# ResetCircuit.net
KiCad netlist of a schematic drawn in Altium Designer
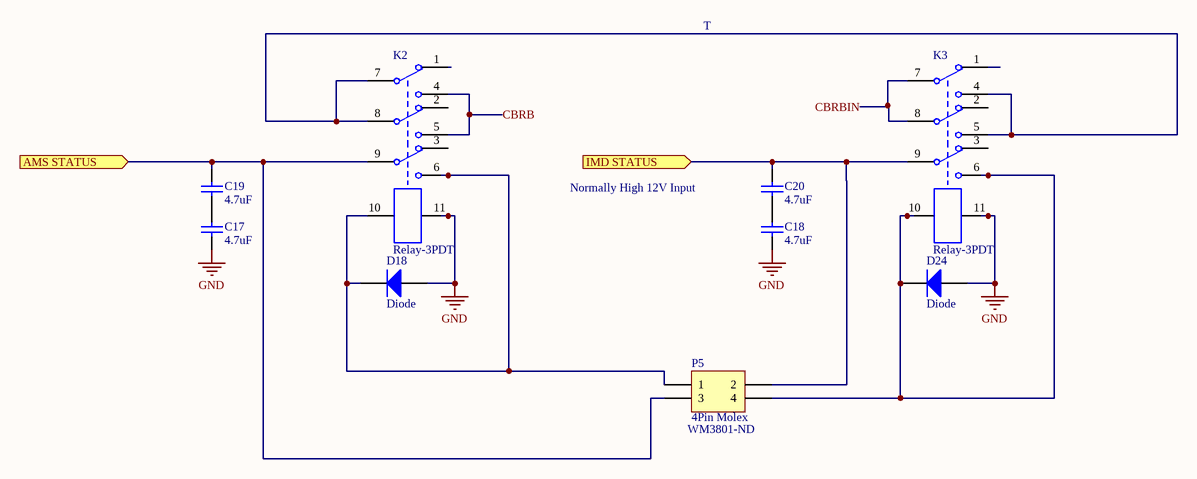
[diagram p0: ResetCircuit.SchDoc]

(export (version "E")
  (design (tool "Eeschema 10.0.6"))
  (components
    (comp (ref "C17")
      (value "4.7uF")
      (footprint "CAPC3216X170N")
      (description "Capacitor (Semiconductor SIM Model)")
      (fields
        (field (name "MANUFACTURER") "Murata")
        (field (name "MANUFACTURER PART NUMBER") "GRM31MR71H105KA88L")
        (field (name "PUBLISHER") "Altium Limited")
      )
      (libsource (lib "Candunio") (part "Cap Semi"))
    )
    (comp (ref "C18")
      (value "4.7uF")
      (footprint "CAPC3216X170N")
      (description "Capacitor (Semiconductor SIM Model)")
      (fields
        (field (name "MANUFACTURER") "Murata")
        (field (name "MANUFACTURER PART NUMBER") "GRM31MR71H105KA88L")
        (field (name "PUBLISHER") "Altium Limited")
      )
      (libsource (lib "Candunio") (part "Cap Semi"))
    )
    (comp (ref "C19")
      (value "4.7uF")
      (footprint "CAPC3216X170N")
      (description "Capacitor (Semiconductor SIM Model)")
      (fields
        (field (name "MANUFACTURER") "Murata")
        (field (name "MANUFACTURER PART NUMBER") "GRM31MR71H105KA88L")
        (field (name "PUBLISHER") "Altium Limited")
      )
      (libsource (lib "Candunio") (part "Cap Semi"))
    )
    (comp (ref "C20")
      (value "4.7uF")
      (footprint "CAPC3216X170N")
      (description "Capacitor (Semiconductor SIM Model)")
      (fields
        (field (name "MANUFACTURER") "Murata")
        (field (name "MANUFACTURER PART NUMBER") "GRM31MR71H105KA88L")
        (field (name "PUBLISHER") "Altium Limited")
      )
      (libsource (lib "Candunio") (part "Cap Semi"))
    )
    (comp (ref "D18")
      (value "Diode")
      (footprint "DO-220AA")
      (description "Default Diode")
      (fields (field (name "PUBLISHER") "Altium Limited"))
      (libsource (lib "Candunio") (part "Diode"))
    )
    (comp (ref "D24")
      (value "Diode")
      (footprint "DO-220AA")
      (description "Default Diode")
      (fields (field (name "PUBLISHER") "Altium Limited"))
      (libsource (lib "Candunio") (part "Diode"))
    )
    (comp (ref "K2")
      (value "Relay-3PDT")
      (footprint "55.13")
      (libsource (lib "RESET circuit") (part "Relay-3PDT"))
    )
    (comp (ref "K3")
      (value "Relay-3PDT")
      (footprint "55.13")
      (libsource (lib "RESET circuit") (part "Relay-3PDT"))
    )
    (comp (ref "P5")
      (value "4Pin Molex")
      (footprint "4Pin Molex")
      (fields (field (name "SUPPLIER PART NUMBER") "WM3801-ND"))
      (libsource (lib "PowerDistLib") (part "4Pin Molex"))
    )
  )
  (nets
    (net (code "1") (name "/AMS STATUS") (class "Default")
      (node (ref "C19") (pin "2") (pinfunction "2_2") (pintype "passive"))
      (node (ref "K2") (pin "9") (pinfunction "9_9") (pintype "passive"))
      (node (ref "P5") (pin "3") (pinfunction "3_3") (pintype "passive"))
    )
    (net (code "2") (name "/CBRB") (class "Default")
      (node (ref "K2") (pin "4") (pinfunction "4_4") (pintype "passive"))
      (node (ref "K2") (pin "5") (pinfunction "5_5") (pintype "passive"))
    )
    (net (code "3") (name "/CBRBIN") (class "Default")
      (node (ref "K3") (pin "7") (pinfunction "7_7") (pintype "passive"))
      (node (ref "K3") (pin "8") (pinfunction "8_8") (pintype "passive"))
    )
    (net (code "4") (name "/IMD STATUS") (class "Default")
      (node (ref "C20") (pin "2") (pinfunction "2_2") (pintype "passive"))
      (node (ref "K3") (pin "9") (pinfunction "9_9") (pintype "passive"))
      (node (ref "P5") (pin "2") (pinfunction "2_2") (pintype "passive"))
    )
    (net (code "5") (name "GND") (class "Default")
      (node (ref "C17") (pin "1") (pinfunction "1_1") (pintype "passive"))
      (node (ref "C18") (pin "1") (pinfunction "1_1") (pintype "passive"))
      (node (ref "D18") (pin "1") (pinfunction "A_1") (pintype "passive"))
      (node (ref "D24") (pin "1") (pinfunction "A_1") (pintype "passive"))
      (node (ref "K2") (pin "11") (pinfunction "11_11") (pintype "passive"))
      (node (ref "K3") (pin "11") (pinfunction "11_11") (pintype "passive"))
    )
    (net (code "6") (name "Net-(C17-Pad2)") (class "Default")
      (node (ref "C17") (pin "2") (pinfunction "2_2") (pintype "passive"))
      (node (ref "C19") (pin "1") (pinfunction "1_1") (pintype "passive"))
    )
    (net (code "7") (name "Net-(C18-Pad2)") (class "Default")
      (node (ref "C18") (pin "2") (pinfunction "2_2") (pintype "passive"))
      (node (ref "C20") (pin "1") (pinfunction "1_1") (pintype "passive"))
    )
    (net (code "8") (name "Net-(D18-K)") (class "Default")
      (node (ref "D18") (pin "2") (pinfunction "K_2") (pintype "passive"))
      (node (ref "K2") (pin "10") (pinfunction "10_10") (pintype "passive"))
      (node (ref "K2") (pin "6") (pinfunction "6_6") (pintype "passive"))
      (node (ref "P5") (pin "1") (pinfunction "1_1") (pintype "passive"))
    )
    (net (code "9") (name "Net-(D24-K)") (class "Default")
      (node (ref "D24") (pin "2") (pinfunction "K_2") (pintype "passive"))
      (node (ref "K3") (pin "10") (pinfunction "10_10") (pintype "passive"))
      (node (ref "K3") (pin "6") (pinfunction "6_6") (pintype "passive"))
      (node (ref "P5") (pin "4") (pinfunction "4_4") (pintype "passive"))
    )
    (net (code "10") (name "Net-(K2-Pad7)") (class "Default")
      (node (ref "K2") (pin "7") (pinfunction "7_7") (pintype "passive"))
      (node (ref "K2") (pin "8") (pinfunction "8_8") (pintype "passive"))
      (node (ref "K3") (pin "4") (pinfunction "4_4") (pintype "passive"))
      (node (ref "K3") (pin "5") (pinfunction "5_5") (pintype "passive"))
    )
    (net (code "11") (name "unconnected-(K2-Pad1)") (class "Default")
      (node (ref "K2") (pin "1") (pinfunction "1_1") (pintype "passive"))
    )
    (net (code "12") (name "unconnected-(K2-Pad2)") (class "Default")
      (node (ref "K2") (pin "2") (pinfunction "2_2") (pintype "passive"))
    )
    (net (code "13") (name "unconnected-(K2-Pad3)") (class "Default")
      (node (ref "K2") (pin "3") (pinfunction "3_3") (pintype "passive"))
    )
    (net (code "14") (name "unconnected-(K3-Pad1)") (class "Default")
      (node (ref "K3") (pin "1") (pinfunction "1_1") (pintype "passive"))
    )
    (net (code "15") (name "unconnected-(K3-Pad2)") (class "Default")
      (node (ref "K3") (pin "2") (pinfunction "2_2") (pintype "passive"))
    )
    (net (code "16") (name "unconnected-(K3-Pad3)") (class "Default")
      (node (ref "K3") (pin "3") (pinfunction "3_3") (pintype "passive"))
    )
  )
)
